# Main_Board_v2.net
KiCad netlist of a schematic drawn in EAGLE
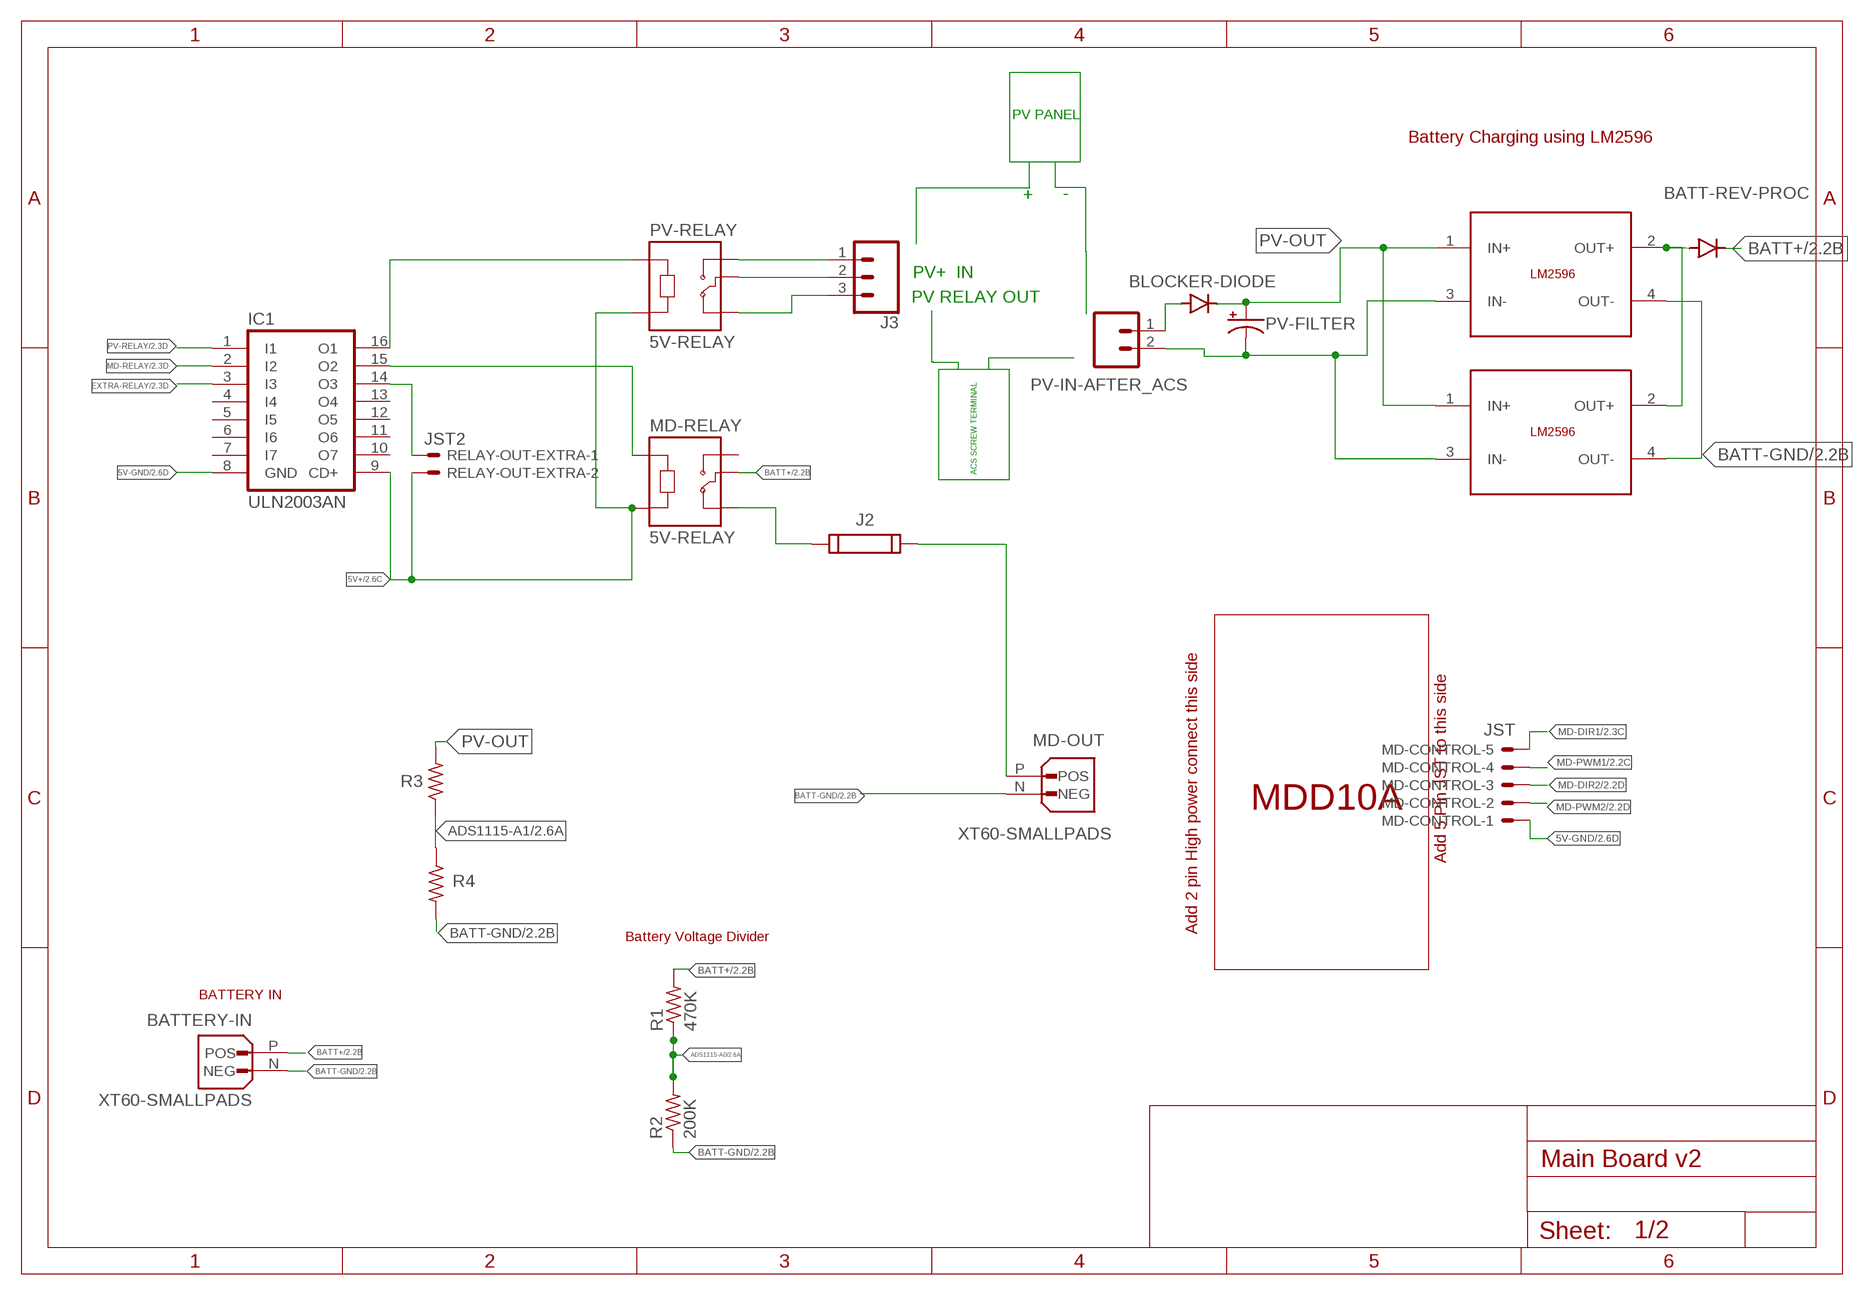
[diagram p0: schematic, sheet 1]
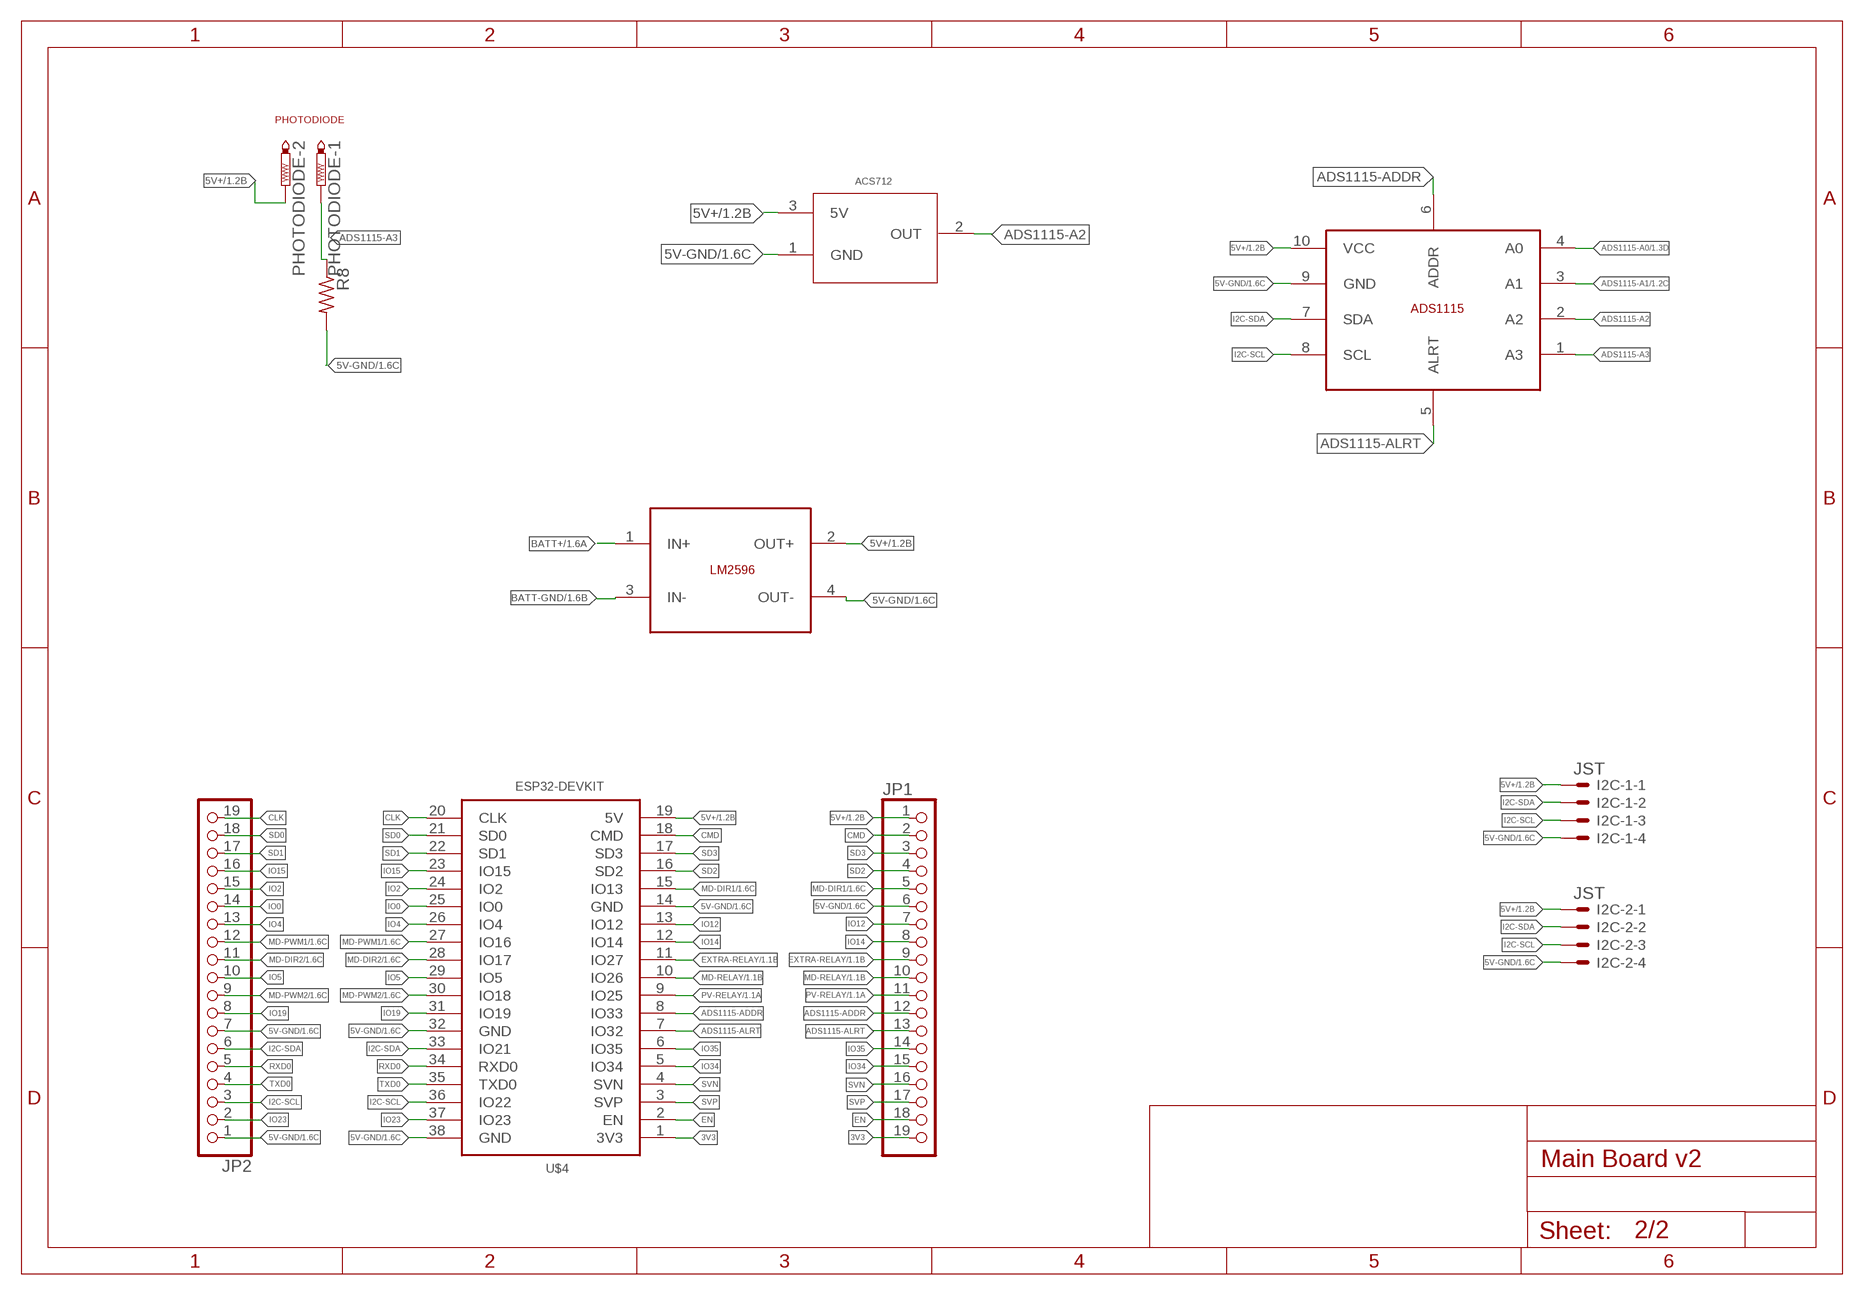
[diagram p1: schematic, sheet 2]

(export (version "E")
  (design (tool "Eeschema 10.0.6"))
  (components
    (comp (ref "I2C-1")
      (value "JST")
      (footprint "eagle-import:JST-XH-04-PACKAGE-LONG-PAD")
      (libsource (lib "eagle-import") (part "JST-XH-04-PIN-LONG-PAD"))
    )
    (comp (ref "I2C-2")
      (value "JST")
      (footprint "eagle-import:JST-XH-04-PACKAGE-LONG-PAD")
      (libsource (lib "eagle-import") (part "JST-XH-04-PIN-LONG-PAD"))
    )
    (comp (ref "JP1")
      (value "PINHD-1X19")
      (footprint "eagle-import:1X19")
      (libsource (lib "eagle-import") (part "PINHD-1X19"))
    )
    (comp (ref "JP2")
      (value "PINHD-1X19")
      (footprint "eagle-import:1X19")
      (libsource (lib "eagle-import") (part "PINHD-1X19"))
    )
    (comp (ref "PHOTODIODE")
      (value "PTR2")
      (footprint "eagle-import:P2-38-17")
      (libsource (lib "eagle-import") (part "PTR2"))
    )
    (comp (ref "R8")
      (value "R-US_0309/12")
      (footprint "eagle-import:0309_12")
      (libsource (lib "eagle-import") (part "R-US_0309/12"))
    )
    (comp (ref "U$4")
      (value "ESP32-DEVKIT")
      (footprint "eagle-import:ESP32-38PINS")
      (libsource (lib "eagle-import") (part "ESP32-DEVKIT"))
    )
    (comp (ref "U$5")
      (value "ACS712-MODULE")
      (footprint "eagle-import:ACS712-MODULE")
      (libsource (lib "eagle-import") (part "ACS712-MODULE"))
    )
    (comp (ref "U$6")
      (value "ADS1115-MODULE")
      (footprint "eagle-import:ADS1115-MODULE")
      (libsource (lib "eagle-import") (part "ADS1115-MODULE"))
    )
    (comp (ref "U$8")
      (value "LM2596-MODULE")
      (footprint "eagle-import:LM2596-MODULE")
      (libsource (lib "eagle-import") (part "LM2596-MODULE"))
    )
    (comp (ref "BATT-REV-PROC")
      (value "1N5400")
      (footprint "eagle-import:DO201-15")
      (libsource (lib "eagle-import") (part "1N5400"))
    )
    (comp (ref "BATTERY-IN")
      (value "XT60-SMALLPADS")
      (footprint "eagle-import:XT-60-SMALLPADS")
      (libsource (lib "eagle-import") (part "XT60-SMALLPADS"))
    )
    (comp (ref "BLOCKER-DIODE")
      (value "1N5400")
      (footprint "eagle-import:DO201-15")
      (libsource (lib "eagle-import") (part "1N5400"))
    )
    (comp (ref "IC1")
      (value "ULN2003AN")
      (footprint "eagle-import:DIL16")
      (fields (field (name "MF") "STMicroelectronics") (field (name "MP") "ULN2003A"))
      (libsource (lib "eagle-import") (part "ULN2003AN"))
    )
    (comp (ref "J2")
      (value "696101000002")
      (footprint "eagle-import:696101000002")
      (libsource (lib "eagle-import") (part "696101000002"))
    )
    (comp (ref "J3")
      (value "CONN_03SCREW_LOCK")
      (footprint "eagle-import:SCREWTERMINAL-3.5MM-3_LOCK.007S")
      (libsource (lib "eagle-import") (part "CONN_03SCREW_LOCK"))
    )
    (comp (ref "MD-CONTROL")
      (value "JST")
      (footprint "eagle-import:JST-XH-05-PACKAGE-LONG-PAD")
      (libsource (lib "eagle-import") (part "JST-XH-05-PIN-LONG-PAD"))
    )
    (comp (ref "MD-OUT")
      (value "XT60-SMALLPADS")
      (footprint "eagle-import:XT-60-SMALLPADS")
      (libsource (lib "eagle-import") (part "XT60-SMALLPADS"))
    )
    (comp (ref "MD-RELAY")
      (value "5V-RELAY")
      (footprint "eagle-import:RELAY-SRD-05VDC-SL-C")
      (fields (field (name "MF") "Songle Relay") (field (name "MP") "SRD-05VDC-SL-C"))
      (libsource (lib "eagle-import") (part "5V-RELAY"))
    )
    (comp (ref "PV-FILTER")
      (value "CPOL-USE5-6")
      (footprint "eagle-import:E5-6")
      (libsource (lib "eagle-import") (part "CPOL-USE5-6"))
    )
    (comp (ref "PV-IN-AFTER_ACS")
      (value "CONN_023.5MM")
      (footprint "eagle-import:SCREWTERMINAL-3.5MM-2")
      (libsource (lib "eagle-import") (part "CONN_023.5MM"))
    )
    (comp (ref "PV-RELAY")
      (value "5V-RELAY")
      (footprint "eagle-import:RELAY-SRD-05VDC-SL-C")
      (fields (field (name "MF") "Songle Relay") (field (name "MP") "SRD-05VDC-SL-C"))
      (libsource (lib "eagle-import") (part "5V-RELAY"))
    )
    (comp (ref "R1")
      (value "470K")
      (footprint "eagle-import:0309_12")
      (libsource (lib "eagle-import") (part "R-US_0309/12"))
    )
    (comp (ref "R2")
      (value "200K")
      (footprint "eagle-import:0309_12")
      (libsource (lib "eagle-import") (part "R-US_0309/12"))
    )
    (comp (ref "R3")
      (value "R-US_0309/12")
      (footprint "eagle-import:0309_12")
      (libsource (lib "eagle-import") (part "R-US_0309/12"))
    )
    (comp (ref "R4")
      (value "R-US_0309/12")
      (footprint "eagle-import:0309_12")
      (libsource (lib "eagle-import") (part "R-US_0309/12"))
    )
    (comp (ref "RELAY-OUT-EXTRA")
      (value "JST2")
      (footprint "eagle-import:JST-XH-02-PACKAGE-LONG-PAD")
      (libsource (lib "eagle-import") (part "JST-XH-02-PIN-LONG-PAD"))
    )
    (comp (ref "U$1")
      (value "LM2596-MODULE")
      (footprint "eagle-import:LM2596-MODULE")
      (libsource (lib "eagle-import") (part "LM2596-MODULE"))
    )
    (comp (ref "U$2")
      (value "LM2596-MODULE")
      (footprint "eagle-import:LM2596-MODULE")
      (libsource (lib "eagle-import") (part "LM2596-MODULE"))
    )
    (comp (ref "U$7")
      (value "MDD10A-MODULE")
      (footprint "eagle-import:MDD10A")
      (libsource (lib "eagle-import") (part "MDD10A-MODULE"))
    )
  )
  (nets
    (net (code "1") (name "3V3") (class "Default")
      (node (ref "JP1") (pin "19") (pinfunction "19_19") (pintype "passive"))
      (node (ref "U$4") (pin "1") (pinfunction "3V3_1") (pintype "bidirectional"))
    )
    (net (code "2") (name "5V+") (class "Default")
      (node (ref "I2C-1") (pin "1") (pinfunction "S_1") (pintype "passive"))
      (node (ref "I2C-2") (pin "1") (pinfunction "S_1") (pintype "passive"))
      (node (ref "IC1") (pin "9") (pinfunction "CD+_9") (pintype "passive"))
      (node (ref "JP1") (pin "1") (pinfunction "1_1") (pintype "passive"))
      (node (ref "MD-RELAY") (pin "A2") (pinfunction "A2_A2") (pintype "passive"))
      (node (ref "PHOTODIODE") (pin "TP-2") (pinfunction "TP_TP-2") (pintype "input"))
      (node (ref "PV-RELAY") (pin "A2") (pinfunction "A2_A2") (pintype "passive"))
      (node (ref "RELAY-OUT-EXTRA") (pin "2") (pinfunction "S_2") (pintype "passive"))
      (node (ref "U$4") (pin "19") (pinfunction "5V_19") (pintype "bidirectional"))
      (node (ref "U$5") (pin "3") (pinfunction "5V_3") (pintype "bidirectional"))
      (node (ref "U$6") (pin "10") (pinfunction "VCC_10") (pintype "bidirectional"))
      (node (ref "U$8") (pin "2") (pinfunction "OUT+_2") (pintype "bidirectional"))
    )
    (net (code "3") (name "5V-GND") (class "Default")
      (node (ref "I2C-1") (pin "4") (pinfunction "S_4") (pintype "passive"))
      (node (ref "I2C-2") (pin "4") (pinfunction "S_4") (pintype "passive"))
      (node (ref "IC1") (pin "8") (pinfunction "GND_8") (pintype "power_in"))
      (node (ref "JP1") (pin "6") (pinfunction "6_6") (pintype "passive"))
      (node (ref "JP2") (pin "1") (pinfunction "1_1") (pintype "passive"))
      (node (ref "JP2") (pin "7") (pinfunction "7_7") (pintype "passive"))
      (node (ref "MD-CONTROL") (pin "1") (pinfunction "S_1") (pintype "passive"))
      (node (ref "R8") (pin "2") (pinfunction "2_2") (pintype "passive"))
      (node (ref "U$4") (pin "14") (pinfunction "GND_14") (pintype "bidirectional"))
      (node (ref "U$4") (pin "32") (pinfunction "GND_32") (pintype "bidirectional"))
      (node (ref "U$4") (pin "38") (pinfunction "GND_38") (pintype "bidirectional"))
      (node (ref "U$5") (pin "1") (pinfunction "GND_1") (pintype "bidirectional"))
      (node (ref "U$6") (pin "9") (pinfunction "GND_9") (pintype "bidirectional"))
      (node (ref "U$8") (pin "4") (pinfunction "OUT-_4") (pintype "bidirectional"))
    )
    (net (code "4") (name "ADS1115-A0") (class "Default")
      (node (ref "R1") (pin "1") (pinfunction "1_1") (pintype "passive"))
      (node (ref "R2") (pin "2") (pinfunction "2_2") (pintype "passive"))
      (node (ref "U$6") (pin "4") (pinfunction "A0_4") (pintype "bidirectional"))
    )
    (net (code "5") (name "ADS1115-A1") (class "Default")
      (node (ref "R3") (pin "1") (pinfunction "1_1") (pintype "passive"))
      (node (ref "R4") (pin "1") (pinfunction "1_1") (pintype "passive"))
      (node (ref "U$6") (pin "3") (pinfunction "A1_3") (pintype "bidirectional"))
    )
    (net (code "6") (name "ADS1115-A2") (class "Default")
      (node (ref "U$5") (pin "2") (pinfunction "OUT_2") (pintype "bidirectional"))
      (node (ref "U$6") (pin "2") (pinfunction "A2_2") (pintype "bidirectional"))
    )
    (net (code "7") (name "ADS1115-A3") (class "Default")
      (node (ref "PHOTODIODE") (pin "TP-1") (pinfunction "TP_TP-1") (pintype "input"))
      (node (ref "R8") (pin "1") (pinfunction "1_1") (pintype "passive"))
      (node (ref "U$6") (pin "1") (pinfunction "A3_1") (pintype "bidirectional"))
    )
    (net (code "8") (name "ADS1115-ADDR") (class "Default")
      (node (ref "JP1") (pin "12") (pinfunction "12_12") (pintype "passive"))
      (node (ref "U$4") (pin "8") (pinfunction "IO33_8") (pintype "bidirectional"))
      (node (ref "U$6") (pin "6") (pinfunction "ADDR_6") (pintype "bidirectional"))
    )
    (net (code "9") (name "ADS1115-ALRT") (class "Default")
      (node (ref "JP1") (pin "13") (pinfunction "13_13") (pintype "passive"))
      (node (ref "U$4") (pin "7") (pinfunction "IO32_7") (pintype "bidirectional"))
      (node (ref "U$6") (pin "5") (pinfunction "ALRT_5") (pintype "bidirectional"))
    )
    (net (code "10") (name "BATT+") (class "Default")
      (node (ref "BATT-REV-PROC") (pin "C") (pinfunction "C_C") (pintype "passive"))
      (node (ref "BATTERY-IN") (pin "P") (pinfunction "POS_P") (pintype "passive"))
      (node (ref "MD-RELAY") (pin "COM") (pinfunction "COM_COM") (pintype "passive"))
      (node (ref "R1") (pin "2") (pinfunction "2_2") (pintype "passive"))
      (node (ref "U$8") (pin "1") (pinfunction "IN+_1") (pintype "bidirectional"))
    )
    (net (code "11") (name "BATT-GND") (class "Default")
      (node (ref "BATTERY-IN") (pin "N") (pinfunction "NEG_N") (pintype "passive"))
      (node (ref "MD-OUT") (pin "N") (pinfunction "NEG_N") (pintype "passive"))
      (node (ref "R2") (pin "1") (pinfunction "1_1") (pintype "passive"))
      (node (ref "R4") (pin "2") (pinfunction "2_2") (pintype "passive"))
      (node (ref "U$1") (pin "4") (pinfunction "OUT-_4") (pintype "bidirectional"))
      (node (ref "U$2") (pin "4") (pinfunction "OUT-_4") (pintype "bidirectional"))
      (node (ref "U$8") (pin "3") (pinfunction "IN-_3") (pintype "bidirectional"))
    )
    (net (code "12") (name "CLK") (class "Default")
      (node (ref "JP2") (pin "19") (pinfunction "19_19") (pintype "passive"))
      (node (ref "U$4") (pin "20") (pinfunction "CLK_20") (pintype "bidirectional"))
    )
    (net (code "13") (name "CMD") (class "Default")
      (node (ref "JP1") (pin "2") (pinfunction "2_2") (pintype "passive"))
      (node (ref "U$4") (pin "18") (pinfunction "CMD_18") (pintype "bidirectional"))
    )
    (net (code "14") (name "EN") (class "Default")
      (node (ref "JP1") (pin "18") (pinfunction "18_18") (pintype "passive"))
      (node (ref "U$4") (pin "2") (pinfunction "EN_2") (pintype "bidirectional"))
    )
    (net (code "15") (name "EXTRA-RELAY") (class "Default")
      (node (ref "IC1") (pin "3") (pinfunction "I3_3") (pintype "input"))
      (node (ref "JP1") (pin "9") (pinfunction "9_9") (pintype "passive"))
      (node (ref "U$4") (pin "11") (pinfunction "IO27_11") (pintype "bidirectional"))
    )
    (net (code "16") (name "I2C-SCL") (class "Default")
      (node (ref "I2C-1") (pin "3") (pinfunction "S_3") (pintype "passive"))
      (node (ref "I2C-2") (pin "3") (pinfunction "S_3") (pintype "passive"))
      (node (ref "JP2") (pin "3") (pinfunction "3_3") (pintype "passive"))
      (node (ref "U$4") (pin "36") (pinfunction "IO22_36") (pintype "bidirectional"))
      (node (ref "U$6") (pin "8") (pinfunction "SCL_8") (pintype "bidirectional"))
    )
    (net (code "17") (name "I2C-SDA") (class "Default")
      (node (ref "I2C-1") (pin "2") (pinfunction "S_2") (pintype "passive"))
      (node (ref "I2C-2") (pin "2") (pinfunction "S_2") (pintype "passive"))
      (node (ref "JP2") (pin "6") (pinfunction "6_6") (pintype "passive"))
      (node (ref "U$4") (pin "33") (pinfunction "IO21_33") (pintype "bidirectional"))
      (node (ref "U$6") (pin "7") (pinfunction "SDA_7") (pintype "bidirectional"))
    )
    (net (code "18") (name "IO0") (class "Default")
      (node (ref "JP2") (pin "14") (pinfunction "14_14") (pintype "passive"))
      (node (ref "U$4") (pin "25") (pinfunction "IO0_25") (pintype "bidirectional"))
    )
    (net (code "19") (name "IO2") (class "Default")
      (node (ref "JP2") (pin "15") (pinfunction "15_15") (pintype "passive"))
      (node (ref "U$4") (pin "24") (pinfunction "IO2_24") (pintype "bidirectional"))
    )
    (net (code "20") (name "IO4") (class "Default")
      (node (ref "JP2") (pin "13") (pinfunction "13_13") (pintype "passive"))
      (node (ref "U$4") (pin "26") (pinfunction "IO4_26") (pintype "bidirectional"))
    )
    (net (code "21") (name "IO5") (class "Default")
      (node (ref "JP2") (pin "10") (pinfunction "10_10") (pintype "passive"))
      (node (ref "U$4") (pin "29") (pinfunction "IO5_29") (pintype "bidirectional"))
    )
    (net (code "22") (name "IO12") (class "Default")
      (node (ref "JP1") (pin "7") (pinfunction "7_7") (pintype "passive"))
      (node (ref "U$4") (pin "13") (pinfunction "IO12_13") (pintype "bidirectional"))
    )
    (net (code "23") (name "IO14") (class "Default")
      (node (ref "JP1") (pin "8") (pinfunction "8_8") (pintype "passive"))
      (node (ref "U$4") (pin "12") (pinfunction "IO14_12") (pintype "bidirectional"))
    )
    (net (code "24") (name "IO15") (class "Default")
      (node (ref "JP2") (pin "16") (pinfunction "16_16") (pintype "passive"))
      (node (ref "U$4") (pin "23") (pinfunction "IO15_23") (pintype "bidirectional"))
    )
    (net (code "25") (name "IO19") (class "Default")
      (node (ref "JP2") (pin "8") (pinfunction "8_8") (pintype "passive"))
      (node (ref "U$4") (pin "31") (pinfunction "IO19_31") (pintype "bidirectional"))
    )
    (net (code "26") (name "IO23") (class "Default")
      (node (ref "JP2") (pin "2") (pinfunction "2_2") (pintype "passive"))
      (node (ref "U$4") (pin "37") (pinfunction "IO23_37") (pintype "bidirectional"))
    )
    (net (code "27") (name "IO34") (class "Default")
      (node (ref "JP1") (pin "15") (pinfunction "15_15") (pintype "passive"))
      (node (ref "U$4") (pin "5") (pinfunction "IO34_5") (pintype "bidirectional"))
    )
    (net (code "28") (name "IO35") (class "Default")
      (node (ref "JP1") (pin "14") (pinfunction "14_14") (pintype "passive"))
      (node (ref "U$4") (pin "6") (pinfunction "IO35_6") (pintype "bidirectional"))
    )
    (net (code "29") (name "MD-DIR1") (class "Default")
      (node (ref "JP1") (pin "5") (pinfunction "5_5") (pintype "passive"))
      (node (ref "MD-CONTROL") (pin "5") (pinfunction "S_5") (pintype "passive"))
      (node (ref "U$4") (pin "15") (pinfunction "IO13_15") (pintype "bidirectional"))
    )
    (net (code "30") (name "MD-DIR2") (class "Default")
      (node (ref "JP2") (pin "11") (pinfunction "11_11") (pintype "passive"))
      (node (ref "MD-CONTROL") (pin "3") (pinfunction "S_3") (pintype "passive"))
      (node (ref "U$4") (pin "28") (pinfunction "IO17_28") (pintype "bidirectional"))
    )
    (net (code "31") (name "MD-PWM1") (class "Default")
      (node (ref "JP2") (pin "12") (pinfunction "12_12") (pintype "passive"))
      (node (ref "MD-CONTROL") (pin "4") (pinfunction "S_4") (pintype "passive"))
      (node (ref "U$4") (pin "27") (pinfunction "IO16_27") (pintype "bidirectional"))
    )
    (net (code "32") (name "MD-PWM2") (class "Default")
      (node (ref "JP2") (pin "9") (pinfunction "9_9") (pintype "passive"))
      (node (ref "MD-CONTROL") (pin "2") (pinfunction "S_2") (pintype "passive"))
      (node (ref "U$4") (pin "30") (pinfunction "IO18_30") (pintype "bidirectional"))
    )
    (net (code "33") (name "MD-RELAY") (class "Default")
      (node (ref "IC1") (pin "2") (pinfunction "I2_2") (pintype "input"))
      (node (ref "JP1") (pin "10") (pinfunction "10_10") (pintype "passive"))
      (node (ref "U$4") (pin "10") (pinfunction "IO26_10") (pintype "bidirectional"))
    )
    (net (code "34") (name "Net-(BLOCKER-DIODE-PadA)") (class "Default")
      (node (ref "BLOCKER-DIODE") (pin "A") (pinfunction "A_A") (pintype "passive"))
      (node (ref "PV-IN-AFTER_ACS") (pin "1") (pinfunction "1_1") (pintype "passive"))
    )
    (net (code "35") (name "Net-(IC1-O1)") (class "Default")
      (node (ref "IC1") (pin "16") (pinfunction "O1_16") (pintype "open_collector"))
      (node (ref "PV-RELAY") (pin "A1") (pinfunction "A1_A1") (pintype "passive"))
    )
    (net (code "36") (name "Net-(IC1-O2)") (class "Default")
      (node (ref "IC1") (pin "15") (pinfunction "O2_15") (pintype "open_collector"))
      (node (ref "MD-RELAY") (pin "A1") (pinfunction "A1_A1") (pintype "passive"))
    )
    (net (code "37") (name "Net-(IC1-O3)") (class "Default")
      (node (ref "IC1") (pin "14") (pinfunction "O3_14") (pintype "open_collector"))
      (node (ref "RELAY-OUT-EXTRA") (pin "1") (pinfunction "S_1") (pintype "passive"))
    )
    (net (code "38") (name "Net-(J2-Pad1)") (class "Default")
      (node (ref "J2") (pin "1") (pinfunction "1_1") (pintype "passive"))
      (node (ref "MD-RELAY") (pin "NC") (pinfunction "NC_NC") (pintype "passive"))
    )
    (net (code "39") (name "Net-(J3-Pad1)") (class "Default")
      (node (ref "J3") (pin "1") (pinfunction "1_1") (pintype "passive"))
      (node (ref "PV-RELAY") (pin "NO") (pinfunction "NO_NO") (pintype "passive"))
    )
    (net (code "40") (name "Net-(J3-Pad2)") (class "Default")
      (node (ref "J3") (pin "2") (pinfunction "2_2") (pintype "passive"))
      (node (ref "PV-RELAY") (pin "COM") (pinfunction "COM_COM") (pintype "passive"))
    )
    (net (code "41") (name "Net-(J3-Pad3)") (class "Default")
      (node (ref "J3") (pin "3") (pinfunction "3_3") (pintype "passive"))
      (node (ref "PV-RELAY") (pin "NC") (pinfunction "NC_NC") (pintype "passive"))
    )
    (net (code "42") (name "Net-(MD-OUT-POS)") (class "Default")
      (node (ref "J2") (pin "2") (pinfunction "2_2") (pintype "passive"))
      (node (ref "MD-OUT") (pin "P") (pinfunction "POS_P") (pintype "passive"))
    )
    (net (code "43") (name "Net-(U$1-IN-)") (class "Default")
      (node (ref "PV-FILTER") (pin "-") (pinfunction "-_-") (pintype "passive"))
      (node (ref "PV-IN-AFTER_ACS") (pin "2") (pinfunction "2_2") (pintype "passive"))
      (node (ref "U$1") (pin "3") (pinfunction "IN-_3") (pintype "bidirectional"))
      (node (ref "U$2") (pin "3") (pinfunction "IN-_3") (pintype "bidirectional"))
    )
    (net (code "44") (name "Net-(U$1-OUT+)") (class "Default")
      (node (ref "BATT-REV-PROC") (pin "A") (pinfunction "A_A") (pintype "passive"))
      (node (ref "U$1") (pin "2") (pinfunction "OUT+_2") (pintype "bidirectional"))
      (node (ref "U$2") (pin "2") (pinfunction "OUT+_2") (pintype "bidirectional"))
    )
    (net (code "45") (name "PV-OUT") (class "Default")
      (node (ref "BLOCKER-DIODE") (pin "C") (pinfunction "C_C") (pintype "passive"))
      (node (ref "PV-FILTER") (pin "+") (pinfunction "+_+") (pintype "passive"))
      (node (ref "R3") (pin "2") (pinfunction "2_2") (pintype "passive"))
      (node (ref "U$1") (pin "1") (pinfunction "IN+_1") (pintype "bidirectional"))
      (node (ref "U$2") (pin "1") (pinfunction "IN+_1") (pintype "bidirectional"))
    )
    (net (code "46") (name "PV-RELAY") (class "Default")
      (node (ref "IC1") (pin "1") (pinfunction "I1_1") (pintype "input"))
      (node (ref "JP1") (pin "11") (pinfunction "11_11") (pintype "passive"))
      (node (ref "U$4") (pin "9") (pinfunction "IO25_9") (pintype "bidirectional"))
    )
    (net (code "47") (name "RXD0") (class "Default")
      (node (ref "JP2") (pin "5") (pinfunction "5_5") (pintype "passive"))
      (node (ref "U$4") (pin "34") (pinfunction "RXD0_34") (pintype "bidirectional"))
    )
    (net (code "48") (name "SD0") (class "Default")
      (node (ref "JP2") (pin "18") (pinfunction "18_18") (pintype "passive"))
      (node (ref "U$4") (pin "21") (pinfunction "SD0_21") (pintype "bidirectional"))
    )
    (net (code "49") (name "SD1") (class "Default")
      (node (ref "JP2") (pin "17") (pinfunction "17_17") (pintype "passive"))
      (node (ref "U$4") (pin "22") (pinfunction "SD1_22") (pintype "bidirectional"))
    )
    (net (code "50") (name "SD2") (class "Default")
      (node (ref "JP1") (pin "4") (pinfunction "4_4") (pintype "passive"))
      (node (ref "U$4") (pin "16") (pinfunction "SD2_16") (pintype "bidirectional"))
    )
    (net (code "51") (name "SD3") (class "Default")
      (node (ref "JP1") (pin "3") (pinfunction "3_3") (pintype "passive"))
      (node (ref "U$4") (pin "17") (pinfunction "SD3_17") (pintype "bidirectional"))
    )
    (net (code "52") (name "SVN") (class "Default")
      (node (ref "JP1") (pin "16") (pinfunction "16_16") (pintype "passive"))
      (node (ref "U$4") (pin "4") (pinfunction "SVN_4") (pintype "bidirectional"))
    )
    (net (code "53") (name "SVP") (class "Default")
      (node (ref "JP1") (pin "17") (pinfunction "17_17") (pintype "passive"))
      (node (ref "U$4") (pin "3") (pinfunction "SVP_3") (pintype "bidirectional"))
    )
    (net (code "54") (name "TXD0") (class "Default")
      (node (ref "JP2") (pin "4") (pinfunction "4_4") (pintype "passive"))
      (node (ref "U$4") (pin "35") (pinfunction "TXD0_35") (pintype "bidirectional"))
    )
    (net (code "55") (name "unconnected-(IC1-I4-Pad4)") (class "Default")
      (node (ref "IC1") (pin "4") (pinfunction "I4_4") (pintype "input"))
    )
    (net (code "56") (name "unconnected-(IC1-I5-Pad5)") (class "Default")
      (node (ref "IC1") (pin "5") (pinfunction "I5_5") (pintype "input"))
    )
    (net (code "57") (name "unconnected-(IC1-I6-Pad6)") (class "Default")
      (node (ref "IC1") (pin "6") (pinfunction "I6_6") (pintype "input"))
    )
    (net (code "58") (name "unconnected-(IC1-I7-Pad7)") (class "Default")
      (node (ref "IC1") (pin "7") (pinfunction "I7_7") (pintype "input"))
    )
    (net (code "59") (name "unconnected-(IC1-O4-Pad13)") (class "Default")
      (node (ref "IC1") (pin "13") (pinfunction "O4_13") (pintype "open_collector"))
    )
    (net (code "60") (name "unconnected-(IC1-O5-Pad12)") (class "Default")
      (node (ref "IC1") (pin "12") (pinfunction "O5_12") (pintype "open_collector"))
    )
    (net (code "61") (name "unconnected-(IC1-O6-Pad11)") (class "Default")
      (node (ref "IC1") (pin "11") (pinfunction "O6_11") (pintype "open_collector"))
    )
    (net (code "62") (name "unconnected-(IC1-O7-Pad10)") (class "Default")
      (node (ref "IC1") (pin "10") (pinfunction "O7_10") (pintype "open_collector"))
    )
    (net (code "63") (name "unconnected-(MD-RELAY-PadNO)") (class "Default")
      (node (ref "MD-RELAY") (pin "NO") (pinfunction "NO_NO") (pintype "passive"))
    )
  )
)
